# Arduino_NG_Ahuratus-SCH.net
KiCad netlist of a schematic drawn in Altium Designer
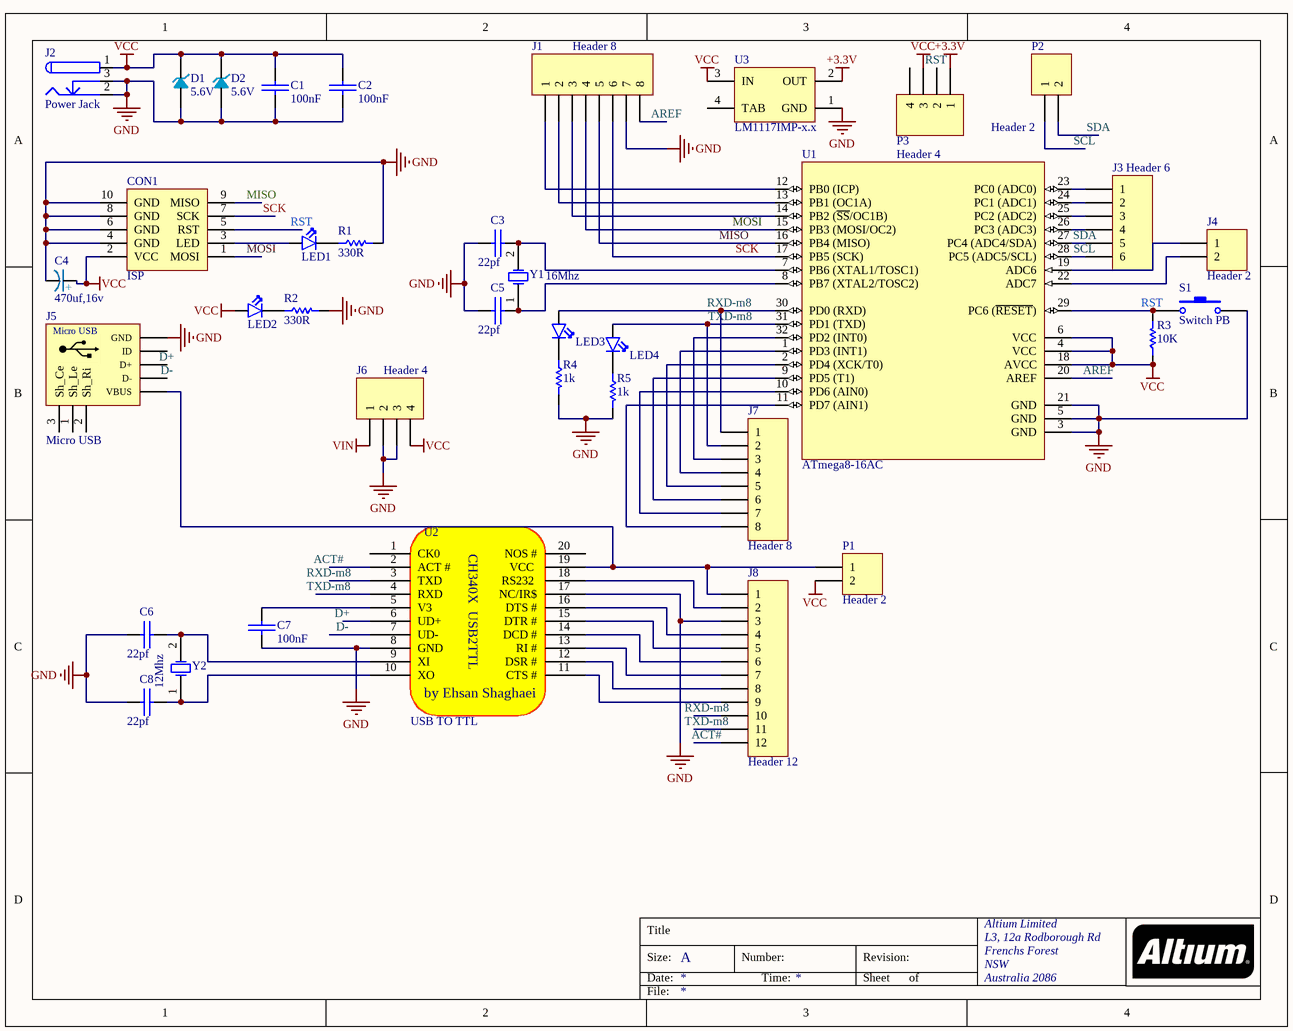
[diagram p0: Arduino NG Ahuratus-SCH.SchDoc]

(export (version "E")
  (design (tool "Eeschema 10.0.6"))
  (components
    (comp (ref "C1")
      (value "100nF")
      (footprint "SMD_CAP_0805")
      (description "Bipolar Capacitor")
      (fields (field (name "VOLTAGE") "100V") (field (name "DESIGNER") "Saeid Jorablo"))
      (libsource (lib "My Library") (part "Cap-Bipolar"))
    )
    (comp (ref "C2")
      (value "100nF")
      (footprint "SMD_CAP_0805")
      (description "Bipolar Capacitor")
      (fields (field (name "VOLTAGE") "100V") (field (name "DESIGNER") "Saeid Jorablo"))
      (libsource (lib "My Library") (part "Cap-Bipolar"))
    )
    (comp (ref "C3")
      (value "22pf")
      (footprint "SMD_CAP_0603")
      (description "Bipolar Capacitor")
      (fields (field (name "VOLTAGE") "100V") (field (name "DESIGNER") "Saeid Jorablo"))
      (libsource (lib "My Library") (part "Cap-Bipolar"))
    )
    (comp (ref "C4")
      (value "Capacitor Polarized")
      (footprint "Electrolytic Capacitor SMD Dia-8 - 100uf")
      (fields (field (name "DESCRIPTION:") "470uf,16v") (field (name "DESIGNER") "Hamed Jafarzadeh ( R2T )"))
      (libsource (lib "R2T Team Library") (part "Capacitor Polarized"))
    )
    (comp (ref "C5")
      (value "22pf")
      (footprint "SMD_CAP_0603")
      (description "Bipolar Capacitor")
      (fields (field (name "VOLTAGE") "100V") (field (name "DESIGNER") "Saeid Jorablo"))
      (libsource (lib "My Library") (part "Cap-Bipolar"))
    )
    (comp (ref "C6")
      (value "22pf")
      (footprint "SMD_CAP_0603")
      (description "Bipolar Capacitor")
      (fields (field (name "VOLTAGE") "100V") (field (name "DESIGNER") "Saeid Jorablo"))
      (libsource (lib "My Library") (part "Cap-Bipolar"))
    )
    (comp (ref "C7")
      (value "100nF")
      (footprint "SMD_CAP_0805")
      (description "Bipolar Capacitor")
      (fields (field (name "VOLTAGE") "100V") (field (name "DESIGNER") "Saeid Jorablo"))
      (libsource (lib "My Library") (part "Cap-Bipolar"))
    )
    (comp (ref "C8")
      (value "22pf")
      (footprint "SMD_CAP_0603")
      (description "Bipolar Capacitor")
      (fields (field (name "VOLTAGE") "100V") (field (name "DESIGNER") "Saeid Jorablo"))
      (libsource (lib "My Library") (part "Cap-Bipolar"))
    )
    (comp (ref "CON1") (value "ISP") (footprint "IDC2_5") (libsource (lib "My_lib_new") (part "ISP")))
    (comp (ref "D1")
      (value "5.6V")
      (footprint "DIOMELF3615N")
      (fields (field (name "DESIGNER") "Hamed Jafarzadeh"))
      (libsource (lib "R2T Team Library") (part "Diode Zener SMD"))
    )
    (comp (ref "D2")
      (value "5.6V")
      (footprint "DIOMELF3615N")
      (fields (field (name "DESIGNER") "Hamed Jafarzadeh"))
      (libsource (lib "R2T Team Library") (part "Diode Zener SMD"))
    )
    (comp (ref "J1")
      (value "Header 8")
      (footprint "HDR1X8")
      (description "Header, 8-Pin")
      (fields (field (name "PUBLISHER") "Altium Limited"))
      (libsource (lib "") (part "Header 8_1"))
    )
    (comp (ref "J2")
      (value "Power Jack")
      (footprint "Power Jack")
      (fields (field (name "DESIGNER") "Saeid Jorablo"))
      (libsource (lib "My Library") (part "Power Jack"))
    )
    (comp (ref "J3")
      (value "Header 6")
      (footprint "HDR1X6")
      (description "Header, 6-Pin")
      (fields (field (name "PUBLISHER") "Altium Limited"))
      (libsource (lib "Miscellaneous Connectors") (part "Header 6"))
    )
    (comp (ref "J4")
      (value "Header 2")
      (footprint "HDR1X2")
      (description "Header, 2-Pin")
      (fields (field (name "PUBLISHER") "Altium Limited"))
      (libsource (lib "") (part "Header 2_1"))
    )
    (comp (ref "J5")
      (value "Micro USB")
      (footprint "MicroUSB")
      (libsource (lib "AHTS-PKG") (part "USB Micro"))
    )
    (comp (ref "J6")
      (value "Header 4")
      (footprint "HDR1X4")
      (description "Header, 4-Pin")
      (fields (field (name "PUBLISHER") "Altium Limited"))
      (libsource (lib "") (part "Header 4_1"))
    )
    (comp (ref "J7")
      (value "Header 8")
      (footprint "HDR1X8")
      (description "Header, 8-Pin")
      (fields (field (name "PUBLISHER") "Altium Limited"))
      (libsource (lib "Miscellaneous Connectors") (part "Header 8"))
    )
    (comp (ref "J8")
      (value "Header 12")
      (footprint "HDR1X12")
      (description "Header, 12-Pin")
      (fields (field (name "PUBLISHER") "Altium Limited"))
      (libsource (lib "Miscellaneous Connectors") (part "Header 12"))
    )
    (comp (ref "LED1")
      (value "LED")
      (footprint "LED0805")
      (fields (field (name "DESIGNER :") "Razi Research Team Of Mashhad - Hamed Jafarzadeh"))
      (libsource (lib "R2T Team Library") (part "LED"))
    )
    (comp (ref "LED2")
      (value "LED")
      (footprint "LED0805")
      (fields (field (name "DESIGNER :") "Razi Research Team Of Mashhad - Hamed Jafarzadeh"))
      (libsource (lib "R2T Team Library") (part "LED"))
    )
    (comp (ref "LED3")
      (value "LED")
      (footprint "LED0805")
      (fields (field (name "DESIGNER :") "Razi Research Team Of Mashhad - Hamed Jafarzadeh"))
      (libsource (lib "R2T Team Library") (part "LED"))
    )
    (comp (ref "LED4")
      (value "LED")
      (footprint "LED0805")
      (fields (field (name "DESIGNER :") "Razi Research Team Of Mashhad - Hamed Jafarzadeh"))
      (libsource (lib "R2T Team Library") (part "LED"))
    )
    (comp (ref "P1")
      (value "Header 2")
      (footprint "HDR1X2")
      (description "Header, 2-Pin")
      (fields (field (name "PUBLISHER") "Altium Limited"))
      (libsource (lib "") (part "Header 2_1"))
    )
    (comp (ref "P2")
      (value "Header 2")
      (footprint "HDR1X2")
      (description "Header, 2-Pin")
      (fields (field (name "PUBLISHER") "Altium Limited"))
      (libsource (lib "Miscellaneous Connectors") (part "Header 2"))
    )
    (comp (ref "P3")
      (value "Header 4")
      (footprint "HDR1X4")
      (description "Header, 4-Pin")
      (fields (field (name "PUBLISHER") "Altium Limited"))
      (libsource (lib "Miscellaneous Connectors") (part "Header 4"))
    )
    (comp (ref "R1")
      (value "330R")
      (footprint "RES 0603 (1608X06L)")
      (description "Resistor")
      (libsource (lib "My Library") (part "Resistor"))
    )
    (comp (ref "R2")
      (value "330R")
      (footprint "RES 0603 (1608X06L)")
      (description "Resistor")
      (libsource (lib "My Library") (part "Resistor"))
    )
    (comp (ref "R3")
      (value "10K")
      (footprint "RES 0603 (1608X06L)")
      (description "Resistor")
      (libsource (lib "My Library") (part "Resistor"))
    )
    (comp (ref "R4")
      (value "1k")
      (footprint "RES 0603 (1608X06L)")
      (description "Resistor")
      (libsource (lib "My Library") (part "Resistor"))
    )
    (comp (ref "R5")
      (value "1k")
      (footprint "RES 0603 (1608X06L)")
      (description "Resistor")
      (libsource (lib "My Library") (part "Resistor"))
    )
    (comp (ref "S1")
      (value "Switch PB")
      (footprint "SW-PB")
      (description "Push Button Switch")
      (libsource (lib "My Library") (part "Switch PB"))
    )
    (comp (ref "U1")
      (value "ATmega8-16AC")
      (footprint "32A_L")
      (description "8-Bit AVR Microcontroller with 8K Bytes of In-System Programmable Flash Memory")
      (fields (field (name "PUBLISHER") "Altium Limited"))
      (libsource (lib "Atmel Microcontroller 8-Bit AVR") (part "ATmega8-16AC"))
    )
    (comp (ref "U2")
      (value "USB TO TTL")
      (footprint "CH340T")
      (fields (field (name "DESIGNER") "Ehsan Shaghaei"))
      (libsource (lib "AHTS-PKG") (part "CH340T"))
    )
    (comp (ref "U3")
      (value "LM1117IMP-x.x")
      (footprint "MP04A_L")
      (description "x.x Volt, 800mA Low-Dropout Linear Regulator, 4-pin SOT-223")
      (fields
        (field (name "PARTNUMBER") "LM1117IMP-3.3")
        (field (name "MANUFACTURER") "National Semiconductor")
        (field (name "PUBLISHER") "Altium Limited")
      )
      (libsource (lib "My Library") (part "LM1117IMP-x.x"))
    )
    (comp (ref "Y1")
      (value "16Mhz")
      (footprint "Crystal SMD")
      (description "XTAL Crystal")
      (libsource (lib "My Library") (part "XTAL"))
    )
    (comp (ref "Y2")
      (value "12Mhz")
      (footprint "Crystal SMD")
      (description "XTAL Crystal")
      (libsource (lib "My Library") (part "XTAL"))
    )
  )
  (nets
    (net (code "1") (name "+3.3V") (class "Default")
      (node (ref "P3") (pin "1") (pinfunction "1_1") (pintype "passive"))
      (node (ref "U3") (pin "2") (pinfunction "OUT_2") (pintype "power_in"))
    )
    (net (code "2") (name "/ACT#") (class "Default")
      (node (ref "J8") (pin "12") (pinfunction "12_12") (pintype "passive"))
      (node (ref "U2") (pin "2") (pinfunction "ACT_#_2") (pintype "passive"))
    )
    (net (code "3") (name "/AREF") (class "Default")
      (node (ref "J1") (pin "8") (pinfunction "8_8") (pintype "passive"))
      (node (ref "U1") (pin "20") (pinfunction "AREF_20") (pintype "passive"))
    )
    (net (code "4") (name "/D+") (class "Default")
      (node (ref "J5") (pin "3-D+") (pinfunction "D+_3-D+") (pintype "passive"))
      (node (ref "U2") (pin "6") (pinfunction "UD+_6") (pintype "passive"))
    )
    (net (code "5") (name "/D-") (class "Default")
      (node (ref "J5") (pin "2-D-") (pinfunction "D-_2-D-") (pintype "power_in"))
      (node (ref "U2") (pin "7") (pinfunction "UD-_7") (pintype "passive"))
    )
    (net (code "6") (name "/MISO") (class "Default")
      (node (ref "CON1") (pin "9") (pinfunction "MISO_9") (pintype "passive"))
      (node (ref "J1") (pin "5") (pinfunction "5_5") (pintype "passive"))
      (node (ref "U1") (pin "16") (pinfunction "PB4_(MISO)_16") (pintype "bidirectional"))
    )
    (net (code "7") (name "/MOSI") (class "Default")
      (node (ref "CON1") (pin "1") (pinfunction "MOSI_1") (pintype "passive"))
      (node (ref "J1") (pin "4") (pinfunction "4_4") (pintype "passive"))
      (node (ref "U1") (pin "15") (pinfunction "PB3_(MOSI/OC2)_15") (pintype "bidirectional"))
    )
    (net (code "8") (name "/RST") (class "Default")
      (node (ref "CON1") (pin "5") (pinfunction "RST_5") (pintype "passive"))
      (node (ref "P3") (pin "2") (pinfunction "2_2") (pintype "passive"))
      (node (ref "R3") (pin "2") (pinfunction "2_2") (pintype "passive"))
      (node (ref "S1") (pin "1") (pinfunction "1_1") (pintype "passive"))
      (node (ref "U1") (pin "29") (pinfunction "PC6_(~{RESET})_29") (pintype "bidirectional"))
    )
    (net (code "9") (name "/RXD-m8") (class "Default")
      (node (ref "J7") (pin "1") (pinfunction "1_1") (pintype "passive"))
      (node (ref "J8") (pin "10") (pinfunction "10_10") (pintype "passive"))
      (node (ref "LED3") (pin "1") (pinfunction "A_1") (pintype "passive"))
      (node (ref "U1") (pin "30") (pinfunction "PD0_(RXD)_30") (pintype "bidirectional"))
      (node (ref "U2") (pin "3") (pinfunction "TXD_3") (pintype "passive"))
    )
    (net (code "10") (name "/SCK") (class "Default")
      (node (ref "CON1") (pin "7") (pinfunction "SCK_7") (pintype "passive"))
      (node (ref "J1") (pin "6") (pinfunction "6_6") (pintype "passive"))
      (node (ref "U1") (pin "17") (pinfunction "PB5_(SCK)_17") (pintype "bidirectional"))
    )
    (net (code "11") (name "/SCL") (class "Default")
      (node (ref "J3") (pin "6") (pinfunction "6_6") (pintype "passive"))
      (node (ref "P2") (pin "1") (pinfunction "1_1") (pintype "passive"))
      (node (ref "U1") (pin "28") (pinfunction "PC5_(ADC5/SCL)_28") (pintype "bidirectional"))
    )
    (net (code "12") (name "/SDA") (class "Default")
      (node (ref "J3") (pin "5") (pinfunction "5_5") (pintype "passive"))
      (node (ref "P2") (pin "2") (pinfunction "2_2") (pintype "passive"))
      (node (ref "U1") (pin "27") (pinfunction "PC4_(ADC4/SDA)_27") (pintype "bidirectional"))
    )
    (net (code "13") (name "/TXD-m8") (class "Default")
      (node (ref "J7") (pin "2") (pinfunction "2_2") (pintype "passive"))
      (node (ref "J8") (pin "11") (pinfunction "11_11") (pintype "passive"))
      (node (ref "LED4") (pin "1") (pinfunction "A_1") (pintype "passive"))
      (node (ref "U1") (pin "31") (pinfunction "PD1_(TXD)_31") (pintype "bidirectional"))
      (node (ref "U2") (pin "4") (pinfunction "RXD_4") (pintype "passive"))
    )
    (net (code "14") (name "GND") (class "Default")
      (node (ref "C1") (pin "2") (pinfunction "-_2") (pintype "passive"))
      (node (ref "C2") (pin "2") (pinfunction "-_2") (pintype "passive"))
      (node (ref "C3") (pin "1") (pinfunction "+_1") (pintype "passive"))
      (node (ref "C4") (pin "2") (pintype "passive"))
      (node (ref "C5") (pin "1") (pinfunction "+_1") (pintype "passive"))
      (node (ref "C6") (pin "1") (pinfunction "+_1") (pintype "passive"))
      (node (ref "C7") (pin "2") (pinfunction "-_2") (pintype "passive"))
      (node (ref "C8") (pin "1") (pinfunction "+_1") (pintype "passive"))
      (node (ref "CON1") (pin "10") (pinfunction "GND_10") (pintype "passive"))
      (node (ref "CON1") (pin "4") (pinfunction "GND_4") (pintype "passive"))
      (node (ref "CON1") (pin "6") (pinfunction "GND_6") (pintype "passive"))
      (node (ref "CON1") (pin "8") (pinfunction "GND_8") (pintype "passive"))
      (node (ref "D1") (pin "2") (pintype "passive"))
      (node (ref "D2") (pin "2") (pintype "passive"))
      (node (ref "J1") (pin "7") (pinfunction "7_7") (pintype "passive"))
      (node (ref "J2") (pin "2") (pinfunction "2_2") (pintype "power_in"))
      (node (ref "J2") (pin "3") (pinfunction "3_3") (pintype "power_in"))
      (node (ref "J5") (pin "5-GND") (pinfunction "GND_5-GND") (pintype "power_in"))
      (node (ref "J6") (pin "2") (pinfunction "2_2") (pintype "passive"))
      (node (ref "J6") (pin "3") (pinfunction "3_3") (pintype "passive"))
      (node (ref "J8") (pin "3") (pinfunction "3_3") (pintype "passive"))
      (node (ref "R1") (pin "2") (pinfunction "2_2") (pintype "passive"))
      (node (ref "R2") (pin "2") (pinfunction "2_2") (pintype "passive"))
      (node (ref "R4") (pin "2") (pinfunction "2_2") (pintype "passive"))
      (node (ref "R5") (pin "2") (pinfunction "2_2") (pintype "passive"))
      (node (ref "S1") (pin "2") (pinfunction "2_2") (pintype "passive"))
      (node (ref "U1") (pin "21") (pinfunction "GND_21") (pintype "power_in"))
      (node (ref "U1") (pin "3") (pinfunction "GND_3") (pintype "power_in"))
      (node (ref "U1") (pin "5") (pinfunction "GND_5") (pintype "power_in"))
      (node (ref "U2") (pin "17") (pinfunction "NC/IR$_17") (pintype "passive"))
      (node (ref "U2") (pin "8") (pinfunction "GND_8") (pintype "passive"))
      (node (ref "U3") (pin "1") (pinfunction "GND_1") (pintype "power_in"))
    )
    (net (code "15") (name "Net-(C3--)") (class "Default")
      (node (ref "C3") (pin "2") (pinfunction "-_2") (pintype "passive"))
      (node (ref "U1") (pin "7") (pinfunction "PB6_(XTAL1/TOSC1)_7") (pintype "bidirectional"))
      (node (ref "Y1") (pin "2") (pinfunction "OSC2_2") (pintype "passive"))
    )
    (net (code "16") (name "Net-(C5--)") (class "Default")
      (node (ref "C5") (pin "2") (pinfunction "-_2") (pintype "passive"))
      (node (ref "U1") (pin "8") (pinfunction "PB7_(XTAL2/TOSC2)_8") (pintype "bidirectional"))
      (node (ref "Y1") (pin "1") (pinfunction "OSC1_1") (pintype "passive"))
    )
    (net (code "17") (name "Net-(C6--)") (class "Default")
      (node (ref "C6") (pin "2") (pinfunction "-_2") (pintype "passive"))
      (node (ref "U2") (pin "9") (pinfunction "XI_9") (pintype "passive"))
      (node (ref "Y2") (pin "2") (pinfunction "OSC2_2") (pintype "passive"))
    )
    (net (code "18") (name "Net-(C7-+)") (class "Default")
      (node (ref "C7") (pin "1") (pinfunction "+_1") (pintype "passive"))
      (node (ref "U2") (pin "5") (pinfunction "V3_5") (pintype "passive"))
    )
    (net (code "19") (name "Net-(C8--)") (class "Default")
      (node (ref "C8") (pin "2") (pinfunction "-_2") (pintype "passive"))
      (node (ref "U2") (pin "10") (pinfunction "XO_10") (pintype "passive"))
      (node (ref "Y2") (pin "1") (pinfunction "OSC1_1") (pintype "passive"))
    )
    (net (code "20") (name "Net-(CON1-LED)") (class "Default")
      (node (ref "CON1") (pin "3") (pinfunction "LED_3") (pintype "passive"))
      (node (ref "LED1") (pin "1") (pinfunction "A_1") (pintype "passive"))
    )
    (net (code "21") (name "Net-(J5-VBUS)") (class "Default")
      (node (ref "J5") (pin "1-VBUS") (pinfunction "VBUS_1-VBUS") (pintype "power_in"))
      (node (ref "J8") (pin "1") (pinfunction "1_1") (pintype "passive"))
      (node (ref "P1") (pin "1") (pinfunction "1_1") (pintype "passive"))
      (node (ref "U2") (pin "19") (pinfunction "VCC_19") (pintype "passive"))
    )
    (net (code "22") (name "Net-(LED1-K)") (class "Default")
      (node (ref "LED1") (pin "2") (pinfunction "K_2") (pintype "passive"))
      (node (ref "R1") (pin "1") (pinfunction "1_1") (pintype "passive"))
    )
    (net (code "23") (name "Net-(LED2-K)") (class "Default")
      (node (ref "LED2") (pin "2") (pinfunction "K_2") (pintype "passive"))
      (node (ref "R2") (pin "1") (pinfunction "1_1") (pintype "passive"))
    )
    (net (code "24") (name "Net-(LED3-K)") (class "Default")
      (node (ref "LED3") (pin "2") (pinfunction "K_2") (pintype "passive"))
      (node (ref "R4") (pin "1") (pinfunction "1_1") (pintype "passive"))
    )
    (net (code "25") (name "Net-(LED4-K)") (class "Default")
      (node (ref "LED4") (pin "2") (pinfunction "K_2") (pintype "passive"))
      (node (ref "R5") (pin "1") (pinfunction "1_1") (pintype "passive"))
    )
    (net (code "26") (name "Net-(U1-ADC6)") (class "Default")
      (node (ref "J4") (pin "1") (pinfunction "1_1") (pintype "passive"))
      (node (ref "U1") (pin "19") (pinfunction "ADC6_19") (pintype "input"))
    )
    (net (code "27") (name "Net-(U1-ADC7)") (class "Default")
      (node (ref "J4") (pin "2") (pinfunction "2_2") (pintype "passive"))
      (node (ref "U1") (pin "22") (pinfunction "ADC7_22") (pintype "input"))
    )
    (net (code "28") (name "Net-(U1-PB0_(ICP))") (class "Default")
      (node (ref "J1") (pin "1") (pinfunction "1_1") (pintype "passive"))
      (node (ref "U1") (pin "12") (pinfunction "PB0_(ICP)_12") (pintype "bidirectional"))
    )
    (net (code "29") (name "Net-(U1-PB1_(OC1A))") (class "Default")
      (node (ref "J1") (pin "2") (pinfunction "2_2") (pintype "passive"))
      (node (ref "U1") (pin "13") (pinfunction "PB1_(OC1A)_13") (pintype "bidirectional"))
    )
    (net (code "30") (name "Net-(U1-PB2_(~{SS}{slash}OC1B))") (class "Default")
      (node (ref "J1") (pin "3") (pinfunction "3_3") (pintype "passive"))
      (node (ref "U1") (pin "14") (pinfunction "PB2_(~{SS}/OC1B)_14") (pintype "bidirectional"))
    )
    (net (code "31") (name "Net-(U1-PC0_(ADC0))") (class "Default")
      (node (ref "J3") (pin "1") (pinfunction "1_1") (pintype "passive"))
      (node (ref "U1") (pin "23") (pinfunction "PC0_(ADC0)_23") (pintype "bidirectional"))
    )
    (net (code "32") (name "Net-(U1-PC1_(ADC1))") (class "Default")
      (node (ref "J3") (pin "2") (pinfunction "2_2") (pintype "passive"))
      (node (ref "U1") (pin "24") (pinfunction "PC1_(ADC1)_24") (pintype "bidirectional"))
    )
    (net (code "33") (name "Net-(U1-PC2_(ADC2))") (class "Default")
      (node (ref "J3") (pin "3") (pinfunction "3_3") (pintype "passive"))
      (node (ref "U1") (pin "25") (pinfunction "PC2_(ADC2)_25") (pintype "bidirectional"))
    )
    (net (code "34") (name "Net-(U1-PC3_(ADC3))") (class "Default")
      (node (ref "J3") (pin "4") (pinfunction "4_4") (pintype "passive"))
      (node (ref "U1") (pin "26") (pinfunction "PC3_(ADC3)_26") (pintype "bidirectional"))
    )
    (net (code "35") (name "Net-(U1-PD2_(INT0))") (class "Default")
      (node (ref "J7") (pin "3") (pinfunction "3_3") (pintype "passive"))
      (node (ref "U1") (pin "32") (pinfunction "PD2_(INT0)_32") (pintype "bidirectional"))
    )
    (net (code "36") (name "Net-(U1-PD3_(INT1))") (class "Default")
      (node (ref "J7") (pin "4") (pinfunction "4_4") (pintype "passive"))
      (node (ref "U1") (pin "1") (pinfunction "PD3_(INT1)_1") (pintype "bidirectional"))
    )
    (net (code "37") (name "Net-(U1-PD4_(XCK{slash}T0))") (class "Default")
      (node (ref "J7") (pin "5") (pinfunction "5_5") (pintype "passive"))
      (node (ref "U1") (pin "2") (pinfunction "PD4_(XCK/T0)_2") (pintype "bidirectional"))
    )
    (net (code "38") (name "Net-(U1-PD5_(T1))") (class "Default")
      (node (ref "J7") (pin "6") (pinfunction "6_6") (pintype "passive"))
      (node (ref "U1") (pin "9") (pinfunction "PD5_(T1)_9") (pintype "bidirectional"))
    )
    (net (code "39") (name "Net-(U1-PD6_(AIN0))") (class "Default")
      (node (ref "J7") (pin "7") (pinfunction "7_7") (pintype "passive"))
      (node (ref "U1") (pin "10") (pinfunction "PD6_(AIN0)_10") (pintype "bidirectional"))
    )
    (net (code "40") (name "Net-(U1-PD7_(AIN1))") (class "Default")
      (node (ref "J7") (pin "8") (pinfunction "8_8") (pintype "passive"))
      (node (ref "U1") (pin "11") (pinfunction "PD7_(AIN1)_11") (pintype "bidirectional"))
    )
    (net (code "41") (name "Net-(U2-CTS_#)") (class "Default")
      (node (ref "J8") (pin "9") (pinfunction "9_9") (pintype "passive"))
      (node (ref "U2") (pin "11") (pinfunction "CTS_#_11") (pintype "passive"))
    )
    (net (code "42") (name "Net-(U2-DCD_#)") (class "Default")
      (node (ref "J8") (pin "6") (pinfunction "6_6") (pintype "passive"))
      (node (ref "U2") (pin "14") (pinfunction "DCD_#_14") (pintype "passive"))
    )
    (net (code "43") (name "Net-(U2-DSR_#)") (class "Default")
      (node (ref "J8") (pin "8") (pinfunction "8_8") (pintype "passive"))
      (node (ref "U2") (pin "12") (pinfunction "DSR_#_12") (pintype "passive"))
    )
    (net (code "44") (name "Net-(U2-DTR_#)") (class "Default")
      (node (ref "J8") (pin "5") (pinfunction "5_5") (pintype "passive"))
      (node (ref "U2") (pin "15") (pinfunction "DTR_#_15") (pintype "passive"))
    )
    (net (code "45") (name "Net-(U2-DTS_#)") (class "Default")
      (node (ref "J8") (pin "4") (pinfunction "4_4") (pintype "passive"))
      (node (ref "U2") (pin "16") (pinfunction "DTS_#_16") (pintype "passive"))
    )
    (net (code "46") (name "Net-(U2-RI_#)") (class "Default")
      (node (ref "J8") (pin "7") (pinfunction "7_7") (pintype "passive"))
      (node (ref "U2") (pin "13") (pinfunction "RI_#_13") (pintype "passive"))
    )
    (net (code "47") (name "Net-(U2-RS232)") (class "Default")
      (node (ref "J8") (pin "2") (pinfunction "2_2") (pintype "passive"))
      (node (ref "U2") (pin "18") (pinfunction "RS232_18") (pintype "passive"))
    )
    (net (code "48") (name "VCC") (class "Default")
      (node (ref "C1") (pin "1") (pinfunction "+_1") (pintype "passive"))
      (node (ref "C2") (pin "1") (pinfunction "+_1") (pintype "passive"))
      (node (ref "C4") (pin "1") (pintype "passive"))
      (node (ref "CON1") (pin "2") (pinfunction "VCC_2") (pintype "passive"))
      (node (ref "D1") (pin "1") (pintype "passive"))
      (node (ref "D2") (pin "1") (pintype "passive"))
      (node (ref "J2") (pin "1") (pinfunction "1_1") (pintype "power_in"))
      (node (ref "J6") (pin "4") (pinfunction "4_4") (pintype "passive"))
      (node (ref "LED2") (pin "1") (pinfunction "A_1") (pintype "passive"))
      (node (ref "P1") (pin "2") (pinfunction "2_2") (pintype "passive"))
      (node (ref "P3") (pin "3") (pinfunction "3_3") (pintype "passive"))
      (node (ref "R3") (pin "1") (pinfunction "1_1") (pintype "passive"))
      (node (ref "U1") (pin "18") (pinfunction "AVCC_18") (pintype "power_in"))
      (node (ref "U1") (pin "4") (pinfunction "VCC_4") (pintype "power_in"))
      (node (ref "U1") (pin "6") (pinfunction "VCC_6") (pintype "power_in"))
      (node (ref "U3") (pin "3") (pinfunction "IN_3") (pintype "power_in"))
    )
    (net (code "49") (name "VIN") (class "Default")
      (node (ref "J6") (pin "1") (pinfunction "1_1") (pintype "passive"))
    )
    (net (code "50") (name "unconnected-(J5-ID-Pad4-ID)") (class "Default")
      (node (ref "J5") (pin "4-ID") (pinfunction "ID_4-ID") (pintype "passive"))
    )
    (net (code "51") (name "unconnected-(J5-Sh_Ce-Pad3)") (class "Default")
      (node (ref "J5") (pin "3") (pinfunction "Sh_Ce_3") (pintype "passive"))
    )
    (net (code "52") (name "unconnected-(J5-Sh_Le-Pad1)") (class "Default")
      (node (ref "J5") (pin "1") (pinfunction "Sh_Le_1") (pintype "passive"))
    )
    (net (code "53") (name "unconnected-(J5-Sh_Ri-Pad2)") (class "Default")
      (node (ref "J5") (pin "2") (pinfunction "Sh_Ri_2") (pintype "passive"))
    )
    (net (code "54") (name "unconnected-(P3-Pad4)") (class "Default")
      (node (ref "P3") (pin "4") (pinfunction "4_4") (pintype "passive"))
    )
    (net (code "55") (name "unconnected-(U2-CK0-Pad1)") (class "Default")
      (node (ref "U2") (pin "1") (pinfunction "CK0_1") (pintype "passive"))
    )
    (net (code "56") (name "unconnected-(U2-NOS_#-Pad20)") (class "Default")
      (node (ref "U2") (pin "20") (pinfunction "NOS_#_20") (pintype "passive"))
    )
    (net (code "57") (name "unconnected-(U3-TAB-Pad4)") (class "Default")
      (node (ref "U3") (pin "4") (pinfunction "TAB_4") (pintype "power_in"))
    )
  )
)
